# unoplustest.net
KiCad netlist of a schematic drawn in EAGLE
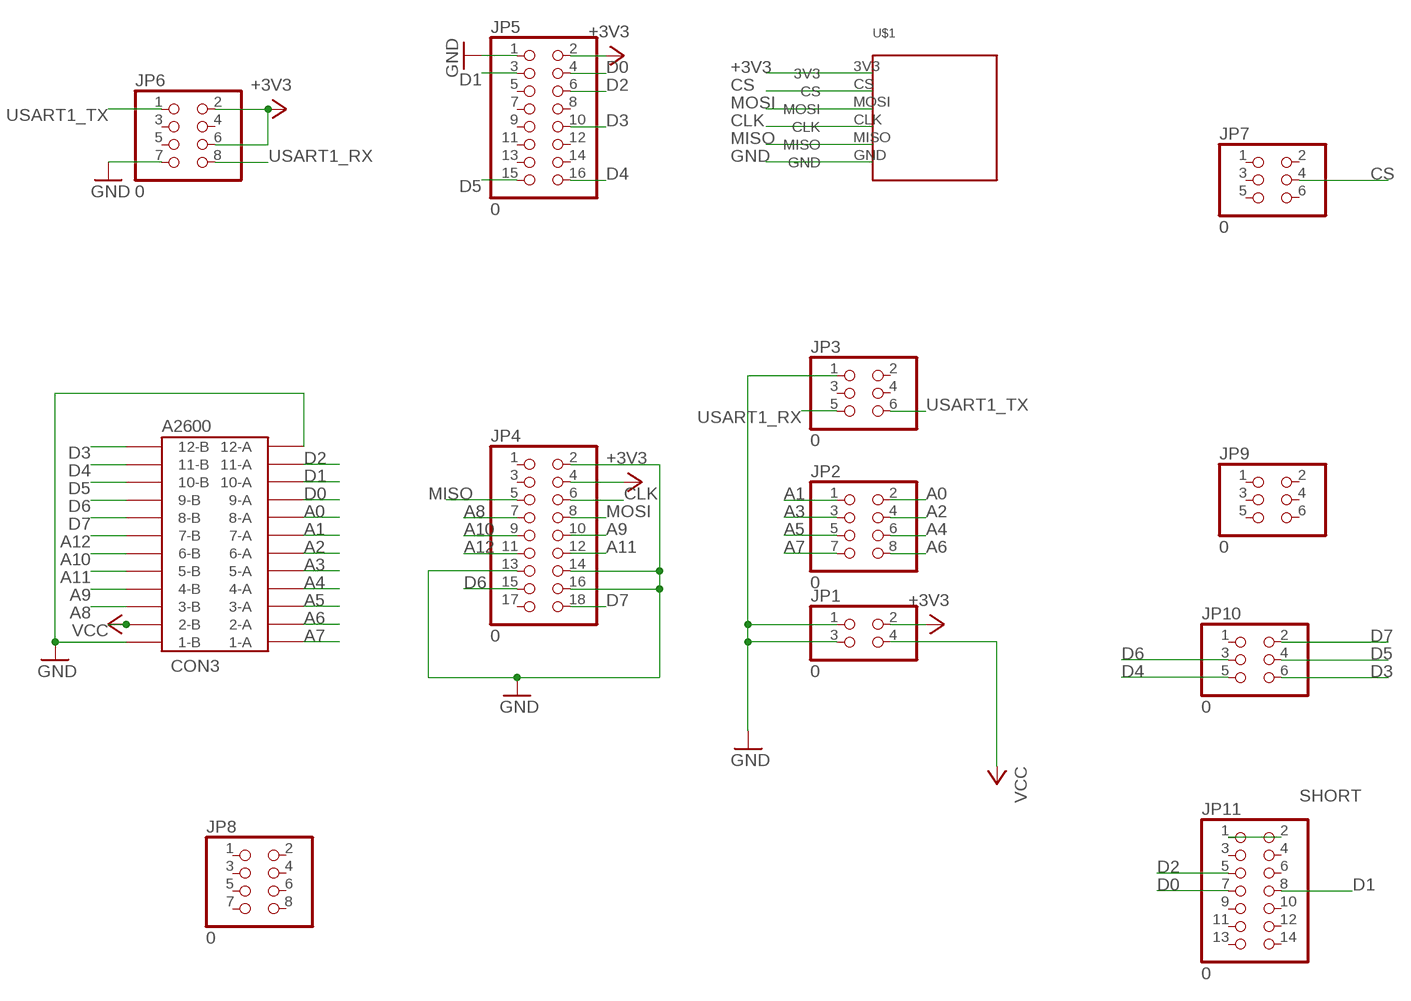
[diagram p0: schematic, sheet 1]

(export (version "E")
  (design (tool "Eeschema 10.0.6"))
  (components
    (comp (ref "CON3")
      (value "A2600")
      (footprint "eagle-import:24PINEDGE-254MM")
      (libsource (lib "eagle-import") (part "24PINEDGE-254MM"))
    )
    (comp (ref "JP1")
      (value "0")
      (footprint "eagle-import:2X02")
      (libsource (lib "eagle-import") (part "PINHD-2X2"))
    )
    (comp (ref "JP2")
      (value "0")
      (footprint "eagle-import:2X04")
      (libsource (lib "eagle-import") (part "PINHD-2X4"))
    )
    (comp (ref "JP3")
      (value "0")
      (footprint "eagle-import:2X03")
      (libsource (lib "eagle-import") (part "PINHD-2X3"))
    )
    (comp (ref "JP4")
      (value "0")
      (footprint "eagle-import:2X09")
      (libsource (lib "eagle-import") (part "PINHD-2X9"))
    )
    (comp (ref "JP5")
      (value "0")
      (footprint "eagle-import:2X08")
      (libsource (lib "eagle-import") (part "PINHD-2X8"))
    )
    (comp (ref "JP6")
      (value "0")
      (footprint "eagle-import:2X04")
      (libsource (lib "eagle-import") (part "PINHD-2X4"))
    )
    (comp (ref "JP7")
      (value "0")
      (footprint "eagle-import:2X03")
      (libsource (lib "eagle-import") (part "pinhead_325_PINHD-2X3"))
    )
    (comp (ref "JP8")
      (value "0")
      (footprint "eagle-import:2X04")
      (libsource (lib "eagle-import") (part "pinhead_325_PINHD-2X4"))
    )
    (comp (ref "JP9")
      (value "0")
      (footprint "eagle-import:2X03")
      (libsource (lib "eagle-import") (part "pinhead_325_PINHD-2X3"))
    )
    (comp (ref "JP10")
      (value "0")
      (footprint "eagle-import:2X03")
      (libsource (lib "eagle-import") (part "pinhead_325_PINHD-2X3"))
    )
    (comp (ref "JP11")
      (value "0")
      (footprint "eagle-import:2X07")
      (libsource (lib "eagle-import") (part "PINHD-2X7"))
    )
    (comp (ref "U$1")
      (value "MICROSD2MICROSD2")
      (footprint "eagle-import:MICROSD_FOOTPRINT")
      (libsource (lib "eagle-import") (part "MICROSD2MICROSD2"))
    )
  )
  (nets
    (net (code "1") (name "+3V3") (class "Default")
      (node (ref "JP1") (pin "2") (pinfunction "2_2") (pintype "passive"))
      (node (ref "JP4") (pin "4") (pinfunction "4_4") (pintype "passive"))
      (node (ref "JP5") (pin "2") (pinfunction "2_2") (pintype "passive"))
      (node (ref "JP6") (pin "2") (pinfunction "2_2") (pintype "passive"))
      (node (ref "JP6") (pin "6") (pinfunction "6_6") (pintype "passive"))
      (node (ref "U$1") (pin "3V3") (pinfunction "3V3_3V3") (pintype "bidirectional"))
    )
    (net (code "2") (name "/A0") (class "Default")
      (node (ref "CON3") (pin "8-A") (pinfunction "8-A_8-A") (pintype "passive"))
      (node (ref "JP2") (pin "2") (pinfunction "2_2") (pintype "passive"))
    )
    (net (code "3") (name "/A1") (class "Default")
      (node (ref "CON3") (pin "7-A") (pinfunction "7-A_7-A") (pintype "passive"))
      (node (ref "JP2") (pin "1") (pinfunction "1_1") (pintype "passive"))
    )
    (net (code "4") (name "/A2") (class "Default")
      (node (ref "CON3") (pin "6-A") (pinfunction "6-A_6-A") (pintype "passive"))
      (node (ref "JP2") (pin "4") (pinfunction "4_4") (pintype "passive"))
    )
    (net (code "5") (name "/A3") (class "Default")
      (node (ref "CON3") (pin "5-A") (pinfunction "5-A_5-A") (pintype "passive"))
      (node (ref "JP2") (pin "3") (pinfunction "3_3") (pintype "passive"))
    )
    (net (code "6") (name "/A4") (class "Default")
      (node (ref "CON3") (pin "4-A") (pinfunction "4-A_4-A") (pintype "passive"))
      (node (ref "JP2") (pin "6") (pinfunction "6_6") (pintype "passive"))
    )
    (net (code "7") (name "/A5") (class "Default")
      (node (ref "CON3") (pin "3-A") (pinfunction "3-A_3-A") (pintype "passive"))
      (node (ref "JP2") (pin "5") (pinfunction "5_5") (pintype "passive"))
    )
    (net (code "8") (name "/A6") (class "Default")
      (node (ref "CON3") (pin "2-A") (pinfunction "2-A_2-A") (pintype "passive"))
      (node (ref "JP2") (pin "8") (pinfunction "8_8") (pintype "passive"))
    )
    (net (code "9") (name "/A7") (class "Default")
      (node (ref "CON3") (pin "1-A") (pinfunction "1-A_1-A") (pintype "passive"))
      (node (ref "JP2") (pin "7") (pinfunction "7_7") (pintype "passive"))
    )
    (net (code "10") (name "/A8") (class "Default")
      (node (ref "CON3") (pin "3-B") (pinfunction "3-B_3-B") (pintype "passive"))
      (node (ref "JP4") (pin "7") (pinfunction "7_7") (pintype "passive"))
    )
    (net (code "11") (name "/A9") (class "Default")
      (node (ref "CON3") (pin "4-B") (pinfunction "4-B_4-B") (pintype "passive"))
      (node (ref "JP4") (pin "10") (pinfunction "10_10") (pintype "passive"))
    )
    (net (code "12") (name "/A10") (class "Default")
      (node (ref "CON3") (pin "6-B") (pinfunction "6-B_6-B") (pintype "passive"))
      (node (ref "JP4") (pin "9") (pinfunction "9_9") (pintype "passive"))
    )
    (net (code "13") (name "/A11") (class "Default")
      (node (ref "CON3") (pin "5-B") (pinfunction "5-B_5-B") (pintype "passive"))
      (node (ref "JP4") (pin "12") (pinfunction "12_12") (pintype "passive"))
    )
    (net (code "14") (name "/A12") (class "Default")
      (node (ref "CON3") (pin "7-B") (pinfunction "7-B_7-B") (pintype "passive"))
      (node (ref "JP4") (pin "11") (pinfunction "11_11") (pintype "passive"))
    )
    (net (code "15") (name "/CLK") (class "Default")
      (node (ref "JP4") (pin "6") (pinfunction "6_6") (pintype "passive"))
      (node (ref "U$1") (pin "CLK") (pinfunction "CLK_CLK") (pintype "bidirectional"))
    )
    (net (code "16") (name "/CS") (class "Default")
      (node (ref "JP7") (pin "4") (pinfunction "4_4") (pintype "passive"))
      (node (ref "U$1") (pin "CS") (pinfunction "CS_CS") (pintype "bidirectional"))
    )
    (net (code "17") (name "/D0") (class "Default")
      (node (ref "CON3") (pin "9-A") (pinfunction "9-A_9-A") (pintype "passive"))
      (node (ref "JP11") (pin "7") (pinfunction "7_7") (pintype "passive"))
      (node (ref "JP5") (pin "4") (pinfunction "4_4") (pintype "passive"))
    )
    (net (code "18") (name "/D1") (class "Default")
      (node (ref "CON3") (pin "10-A") (pinfunction "10-A_10-A") (pintype "passive"))
      (node (ref "JP11") (pin "8") (pinfunction "8_8") (pintype "passive"))
      (node (ref "JP5") (pin "3") (pinfunction "3_3") (pintype "passive"))
    )
    (net (code "19") (name "/D2") (class "Default")
      (node (ref "CON3") (pin "11-A") (pinfunction "11-A_11-A") (pintype "passive"))
      (node (ref "JP11") (pin "5") (pinfunction "5_5") (pintype "passive"))
      (node (ref "JP5") (pin "6") (pinfunction "6_6") (pintype "passive"))
    )
    (net (code "20") (name "/D3") (class "Default")
      (node (ref "CON3") (pin "12-B") (pinfunction "12-B_12-B") (pintype "passive"))
      (node (ref "JP10") (pin "6") (pinfunction "6_6") (pintype "passive"))
      (node (ref "JP5") (pin "10") (pinfunction "10_10") (pintype "passive"))
    )
    (net (code "21") (name "/D4") (class "Default")
      (node (ref "CON3") (pin "11-B") (pinfunction "11-B_11-B") (pintype "passive"))
      (node (ref "JP10") (pin "5") (pinfunction "5_5") (pintype "passive"))
      (node (ref "JP5") (pin "16") (pinfunction "16_16") (pintype "passive"))
    )
    (net (code "22") (name "/D5") (class "Default")
      (node (ref "CON3") (pin "10-B") (pinfunction "10-B_10-B") (pintype "passive"))
      (node (ref "JP10") (pin "4") (pinfunction "4_4") (pintype "passive"))
      (node (ref "JP5") (pin "15") (pinfunction "15_15") (pintype "passive"))
    )
    (net (code "23") (name "/D6") (class "Default")
      (node (ref "CON3") (pin "9-B") (pinfunction "9-B_9-B") (pintype "passive"))
      (node (ref "JP10") (pin "3") (pinfunction "3_3") (pintype "passive"))
      (node (ref "JP4") (pin "15") (pinfunction "15_15") (pintype "passive"))
    )
    (net (code "24") (name "/D7") (class "Default")
      (node (ref "CON3") (pin "8-B") (pinfunction "8-B_8-B") (pintype "passive"))
      (node (ref "JP10") (pin "2") (pinfunction "2_2") (pintype "passive"))
      (node (ref "JP4") (pin "18") (pinfunction "18_18") (pintype "passive"))
    )
    (net (code "25") (name "/MISO") (class "Default")
      (node (ref "JP4") (pin "5") (pinfunction "5_5") (pintype "passive"))
      (node (ref "U$1") (pin "MISO") (pinfunction "MISO_MISO") (pintype "bidirectional"))
    )
    (net (code "26") (name "/MOSI") (class "Default")
      (node (ref "JP4") (pin "8") (pinfunction "8_8") (pintype "passive"))
      (node (ref "U$1") (pin "MOSI") (pinfunction "MOSI_MOSI") (pintype "bidirectional"))
    )
    (net (code "27") (name "/SHORT") (class "Default")
      (node (ref "JP11") (pin "1") (pinfunction "1_1") (pintype "passive"))
      (node (ref "JP11") (pin "2") (pinfunction "2_2") (pintype "passive"))
    )
    (net (code "28") (name "/USART1_RX") (class "Default")
      (node (ref "JP3") (pin "5") (pinfunction "5_5") (pintype "passive"))
      (node (ref "JP6") (pin "8") (pinfunction "8_8") (pintype "passive"))
    )
    (net (code "29") (name "/USART1_TX") (class "Default")
      (node (ref "JP3") (pin "6") (pinfunction "6_6") (pintype "passive"))
      (node (ref "JP6") (pin "1") (pinfunction "1_1") (pintype "passive"))
    )
    (net (code "30") (name "GND") (class "Default")
      (node (ref "CON3") (pin "1-B") (pinfunction "1-B_1-B") (pintype "passive"))
      (node (ref "CON3") (pin "12-A") (pinfunction "12-A_12-A") (pintype "passive"))
      (node (ref "JP1") (pin "1") (pinfunction "1_1") (pintype "passive"))
      (node (ref "JP1") (pin "3") (pinfunction "3_3") (pintype "passive"))
      (node (ref "JP3") (pin "1") (pinfunction "1_1") (pintype "passive"))
      (node (ref "JP4") (pin "13") (pinfunction "13_13") (pintype "passive"))
      (node (ref "JP4") (pin "14") (pinfunction "14_14") (pintype "passive"))
      (node (ref "JP4") (pin "16") (pinfunction "16_16") (pintype "passive"))
      (node (ref "JP4") (pin "2") (pinfunction "2_2") (pintype "passive"))
      (node (ref "JP5") (pin "1") (pinfunction "1_1") (pintype "passive"))
      (node (ref "JP6") (pin "7") (pinfunction "7_7") (pintype "passive"))
      (node (ref "U$1") (pin "GND") (pinfunction "GND_GND") (pintype "bidirectional"))
    )
    (net (code "31") (name "VCC") (class "Default")
      (node (ref "CON3") (pin "2-B") (pinfunction "2-B_2-B") (pintype "passive"))
      (node (ref "JP1") (pin "4") (pinfunction "4_4") (pintype "passive"))
    )
    (net (code "32") (name "unconnected-(JP3-Pad2)") (class "Default")
      (node (ref "JP3") (pin "2") (pinfunction "2_2") (pintype "passive"))
    )
    (net (code "33") (name "unconnected-(JP3-Pad3)") (class "Default")
      (node (ref "JP3") (pin "3") (pinfunction "3_3") (pintype "passive"))
    )
    (net (code "34") (name "unconnected-(JP3-Pad4)") (class "Default")
      (node (ref "JP3") (pin "4") (pinfunction "4_4") (pintype "passive"))
    )
    (net (code "35") (name "unconnected-(JP4-Pad1)") (class "Default")
      (node (ref "JP4") (pin "1") (pinfunction "1_1") (pintype "passive"))
    )
    (net (code "36") (name "unconnected-(JP4-Pad3)") (class "Default")
      (node (ref "JP4") (pin "3") (pinfunction "3_3") (pintype "passive"))
    )
    (net (code "37") (name "unconnected-(JP4-Pad17)") (class "Default")
      (node (ref "JP4") (pin "17") (pinfunction "17_17") (pintype "passive"))
    )
    (net (code "38") (name "unconnected-(JP5-Pad5)") (class "Default")
      (node (ref "JP5") (pin "5") (pinfunction "5_5") (pintype "passive"))
    )
    (net (code "39") (name "unconnected-(JP5-Pad7)") (class "Default")
      (node (ref "JP5") (pin "7") (pinfunction "7_7") (pintype "passive"))
    )
    (net (code "40") (name "unconnected-(JP5-Pad8)") (class "Default")
      (node (ref "JP5") (pin "8") (pinfunction "8_8") (pintype "passive"))
    )
    (net (code "41") (name "unconnected-(JP5-Pad9)") (class "Default")
      (node (ref "JP5") (pin "9") (pinfunction "9_9") (pintype "passive"))
    )
    (net (code "42") (name "unconnected-(JP5-Pad11)") (class "Default")
      (node (ref "JP5") (pin "11") (pinfunction "11_11") (pintype "passive"))
    )
    (net (code "43") (name "unconnected-(JP5-Pad12)") (class "Default")
      (node (ref "JP5") (pin "12") (pinfunction "12_12") (pintype "passive"))
    )
    (net (code "44") (name "unconnected-(JP5-Pad13)") (class "Default")
      (node (ref "JP5") (pin "13") (pinfunction "13_13") (pintype "passive"))
    )
    (net (code "45") (name "unconnected-(JP5-Pad14)") (class "Default")
      (node (ref "JP5") (pin "14") (pinfunction "14_14") (pintype "passive"))
    )
    (net (code "46") (name "unconnected-(JP6-Pad3)") (class "Default")
      (node (ref "JP6") (pin "3") (pinfunction "3_3") (pintype "passive"))
    )
    (net (code "47") (name "unconnected-(JP6-Pad4)") (class "Default")
      (node (ref "JP6") (pin "4") (pinfunction "4_4") (pintype "passive"))
    )
    (net (code "48") (name "unconnected-(JP6-Pad5)") (class "Default")
      (node (ref "JP6") (pin "5") (pinfunction "5_5") (pintype "passive"))
    )
    (net (code "49") (name "unconnected-(JP7-Pad1)") (class "Default")
      (node (ref "JP7") (pin "1") (pinfunction "1_1") (pintype "passive"))
    )
    (net (code "50") (name "unconnected-(JP7-Pad2)") (class "Default")
      (node (ref "JP7") (pin "2") (pinfunction "2_2") (pintype "passive"))
    )
    (net (code "51") (name "unconnected-(JP7-Pad3)") (class "Default")
      (node (ref "JP7") (pin "3") (pinfunction "3_3") (pintype "passive"))
    )
    (net (code "52") (name "unconnected-(JP7-Pad5)") (class "Default")
      (node (ref "JP7") (pin "5") (pinfunction "5_5") (pintype "passive"))
    )
    (net (code "53") (name "unconnected-(JP7-Pad6)") (class "Default")
      (node (ref "JP7") (pin "6") (pinfunction "6_6") (pintype "passive"))
    )
    (net (code "54") (name "unconnected-(JP8-Pad1)") (class "Default")
      (node (ref "JP8") (pin "1") (pinfunction "1_1") (pintype "passive"))
    )
    (net (code "55") (name "unconnected-(JP8-Pad2)") (class "Default")
      (node (ref "JP8") (pin "2") (pinfunction "2_2") (pintype "passive"))
    )
    (net (code "56") (name "unconnected-(JP8-Pad3)") (class "Default")
      (node (ref "JP8") (pin "3") (pinfunction "3_3") (pintype "passive"))
    )
    (net (code "57") (name "unconnected-(JP8-Pad4)") (class "Default")
      (node (ref "JP8") (pin "4") (pinfunction "4_4") (pintype "passive"))
    )
    (net (code "58") (name "unconnected-(JP8-Pad5)") (class "Default")
      (node (ref "JP8") (pin "5") (pinfunction "5_5") (pintype "passive"))
    )
    (net (code "59") (name "unconnected-(JP8-Pad6)") (class "Default")
      (node (ref "JP8") (pin "6") (pinfunction "6_6") (pintype "passive"))
    )
    (net (code "60") (name "unconnected-(JP8-Pad7)") (class "Default")
      (node (ref "JP8") (pin "7") (pinfunction "7_7") (pintype "passive"))
    )
    (net (code "61") (name "unconnected-(JP8-Pad8)") (class "Default")
      (node (ref "JP8") (pin "8") (pinfunction "8_8") (pintype "passive"))
    )
    (net (code "62") (name "unconnected-(JP9-Pad1)") (class "Default")
      (node (ref "JP9") (pin "1") (pinfunction "1_1") (pintype "passive"))
    )
    (net (code "63") (name "unconnected-(JP9-Pad2)") (class "Default")
      (node (ref "JP9") (pin "2") (pinfunction "2_2") (pintype "passive"))
    )
    (net (code "64") (name "unconnected-(JP9-Pad3)") (class "Default")
      (node (ref "JP9") (pin "3") (pinfunction "3_3") (pintype "passive"))
    )
    (net (code "65") (name "unconnected-(JP9-Pad4)") (class "Default")
      (node (ref "JP9") (pin "4") (pinfunction "4_4") (pintype "passive"))
    )
    (net (code "66") (name "unconnected-(JP9-Pad5)") (class "Default")
      (node (ref "JP9") (pin "5") (pinfunction "5_5") (pintype "passive"))
    )
    (net (code "67") (name "unconnected-(JP9-Pad6)") (class "Default")
      (node (ref "JP9") (pin "6") (pinfunction "6_6") (pintype "passive"))
    )
    (net (code "68") (name "unconnected-(JP10-Pad1)") (class "Default")
      (node (ref "JP10") (pin "1") (pinfunction "1_1") (pintype "passive"))
    )
    (net (code "69") (name "unconnected-(JP11-Pad3)") (class "Default")
      (node (ref "JP11") (pin "3") (pinfunction "3_3") (pintype "passive"))
    )
    (net (code "70") (name "unconnected-(JP11-Pad4)") (class "Default")
      (node (ref "JP11") (pin "4") (pinfunction "4_4") (pintype "passive"))
    )
    (net (code "71") (name "unconnected-(JP11-Pad6)") (class "Default")
      (node (ref "JP11") (pin "6") (pinfunction "6_6") (pintype "passive"))
    )
    (net (code "72") (name "unconnected-(JP11-Pad9)") (class "Default")
      (node (ref "JP11") (pin "9") (pinfunction "9_9") (pintype "passive"))
    )
    (net (code "73") (name "unconnected-(JP11-Pad10)") (class "Default")
      (node (ref "JP11") (pin "10") (pinfunction "10_10") (pintype "passive"))
    )
    (net (code "74") (name "unconnected-(JP11-Pad11)") (class "Default")
      (node (ref "JP11") (pin "11") (pinfunction "11_11") (pintype "passive"))
    )
    (net (code "75") (name "unconnected-(JP11-Pad12)") (class "Default")
      (node (ref "JP11") (pin "12") (pinfunction "12_12") (pintype "passive"))
    )
    (net (code "76") (name "unconnected-(JP11-Pad13)") (class "Default")
      (node (ref "JP11") (pin "13") (pinfunction "13_13") (pintype "passive"))
    )
    (net (code "77") (name "unconnected-(JP11-Pad14)") (class "Default")
      (node (ref "JP11") (pin "14") (pinfunction "14_14") (pintype "passive"))
    )
  )
)
